# atuador_heater.net
KiCad netlist of a schematic drawn in Altium Designer
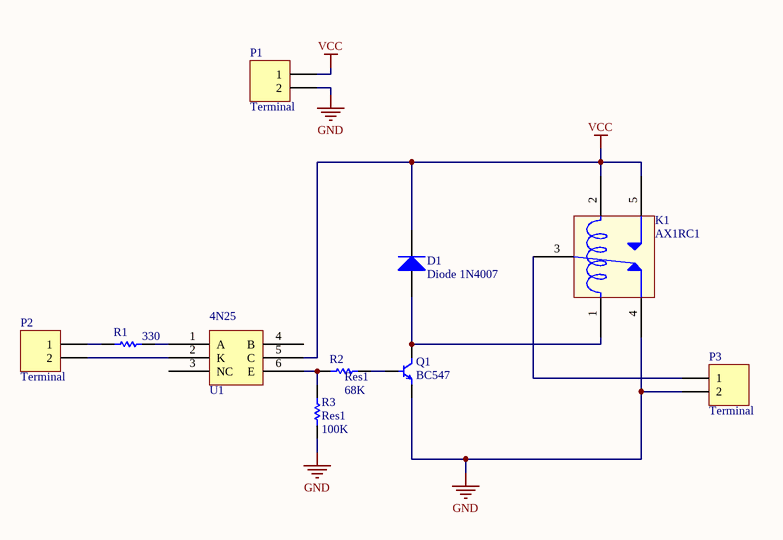
[diagram p0: atuador_heater.SchDoc]

(export (version "E")
  (design (tool "Eeschema 10.0.6"))
  (components
    (comp (ref "D1")
      (value "Diode 1N4007")
      (footprint "DO-41")
      (description "1 Amp General Purpose Rectifier")
      (fields (field (name "PUBLISHER") "Altium Limited"))
      (libsource (lib "Miscellaneous Devices") (part "Diode 1N4007"))
    )
    (comp (ref "K1")
      (value "AX1RC1")
      (footprint "Relay-A")
      (description "Miniature Relay, 15 A, 6 Vdc, 250 Vac")
      (libsource (lib "GPDSE") (part "AX1RC1"))
    )
    (comp (ref "P1")
      (value "Terminal")
      (footprint "KRE_2")
      (description "Terminal Block 1x2")
      (libsource (lib "GPDSE") (part "KRE_2"))
    )
    (comp (ref "P2")
      (value "Terminal")
      (footprint "KRE_2")
      (description "Terminal Block 1x2")
      (libsource (lib "GPDSE") (part "KRE_2"))
    )
    (comp (ref "P3")
      (value "Terminal")
      (footprint "KRE_2")
      (description "Terminal Block 1x2")
      (libsource (lib "") (part "KRE_2_1"))
    )
    (comp (ref "Q1")
      (value "BC547")
      (footprint "TO-92/CBE")
      (description "NPN Epitaxial Silicon Transistor")
      (fields (field (name "COMPLEMENTARY PART") "BC557"))
      (libsource (lib "GPDSE") (part "BC547"))
    )
    (comp (ref "R1")
      (value "330")
      (footprint "AXIAL-0.3")
      (description "Resistor")
      (fields (field (name "Comment") "Res1") (field (name "PUBLISHER") "Altium Limited"))
      (libsource (lib "Miscellaneous Devices") (part "Res1"))
    )
    (comp (ref "R2")
      (value "Res1")
      (footprint "AXIAL-0.3")
      (description "Resistor")
      (fields (field (name "ALTIUM_VALUE") "68K") (field (name "PUBLISHER") "Altium Limited"))
      (libsource (lib "Miscellaneous Devices") (part "Res1"))
    )
    (comp (ref "R3")
      (value "Res1")
      (footprint "AXIAL-0.3")
      (description "Resistor")
      (fields (field (name "ALTIUM_VALUE") "100K") (field (name "PUBLISHER") "Altium Limited"))
      (libsource (lib "Miscellaneous Devices") (part "Res1"))
    )
    (comp (ref "U1") (value "4N25") (footprint "4N25") (libsource (lib "Schlib1") (part "4N25")))
  )
  (nets
    (net (code "1") (name "GND") (class "Default")
      (node (ref "K1") (pin "4") (pinfunction "4_4") (pintype "passive"))
      (node (ref "P1") (pin "2") (pinfunction "2_2") (pintype "passive"))
      (node (ref "P3") (pin "2") (pinfunction "2_2") (pintype "passive"))
      (node (ref "Q1") (pin "E") (pinfunction "E_E") (pintype "passive"))
      (node (ref "R3") (pin "1") (pinfunction "1_1") (pintype "passive"))
    )
    (net (code "2") (name "Net-(D1-A)") (class "Default")
      (node (ref "D1") (pin "1") (pinfunction "A_1") (pintype "passive"))
      (node (ref "K1") (pin "1") (pinfunction "1_1") (pintype "passive"))
      (node (ref "Q1") (pin "C") (pinfunction "C_C") (pintype "passive"))
    )
    (net (code "3") (name "Net-(K1-Pad3)") (class "Default")
      (node (ref "K1") (pin "3") (pinfunction "3_3") (pintype "passive"))
      (node (ref "P3") (pin "1") (pinfunction "1_1") (pintype "passive"))
    )
    (net (code "4") (name "Net-(P2-Pad1)") (class "Default")
      (node (ref "P2") (pin "1") (pinfunction "1_1") (pintype "passive"))
      (node (ref "R1") (pin "1") (pinfunction "1_1") (pintype "passive"))
    )
    (net (code "5") (name "Net-(Q1-PadB)") (class "Default")
      (node (ref "Q1") (pin "B") (pinfunction "B_B") (pintype "passive"))
      (node (ref "R2") (pin "2") (pinfunction "2_2") (pintype "passive"))
    )
    (net (code "6") (name "Net-(U1-A)") (class "Default")
      (node (ref "R1") (pin "2") (pinfunction "2_2") (pintype "passive"))
      (node (ref "U1") (pin "1") (pinfunction "A_1") (pintype "passive"))
    )
    (net (code "7") (name "Net-(U1-E)") (class "Default")
      (node (ref "R2") (pin "1") (pinfunction "1_1") (pintype "passive"))
      (node (ref "R3") (pin "2") (pinfunction "2_2") (pintype "passive"))
      (node (ref "U1") (pin "6") (pinfunction "E_6") (pintype "passive"))
    )
    (net (code "8") (name "Net-(U1-K)") (class "Default")
      (node (ref "P2") (pin "2") (pinfunction "2_2") (pintype "passive"))
      (node (ref "U1") (pin "2") (pinfunction "K_2") (pintype "passive"))
    )
    (net (code "9") (name "VCC") (class "Default")
      (node (ref "D1") (pin "2") (pinfunction "K_2") (pintype "passive"))
      (node (ref "K1") (pin "2") (pinfunction "2_2") (pintype "passive"))
      (node (ref "K1") (pin "5") (pinfunction "5_5") (pintype "passive"))
      (node (ref "P1") (pin "1") (pinfunction "1_1") (pintype "passive"))
      (node (ref "U1") (pin "5") (pinfunction "C_5") (pintype "passive"))
    )
    (net (code "10") (name "unconnected-(U1-B-Pad4)") (class "Default")
      (node (ref "U1") (pin "4") (pinfunction "B_4") (pintype "passive"))
    )
    (net (code "11") (name "unconnected-(U1-NC-Pad3)") (class "Default")
      (node (ref "U1") (pin "3") (pinfunction "NC_3") (pintype "passive"))
    )
  )
)
